# PIC.net
KiCad netlist of a schematic drawn in Altium Designer
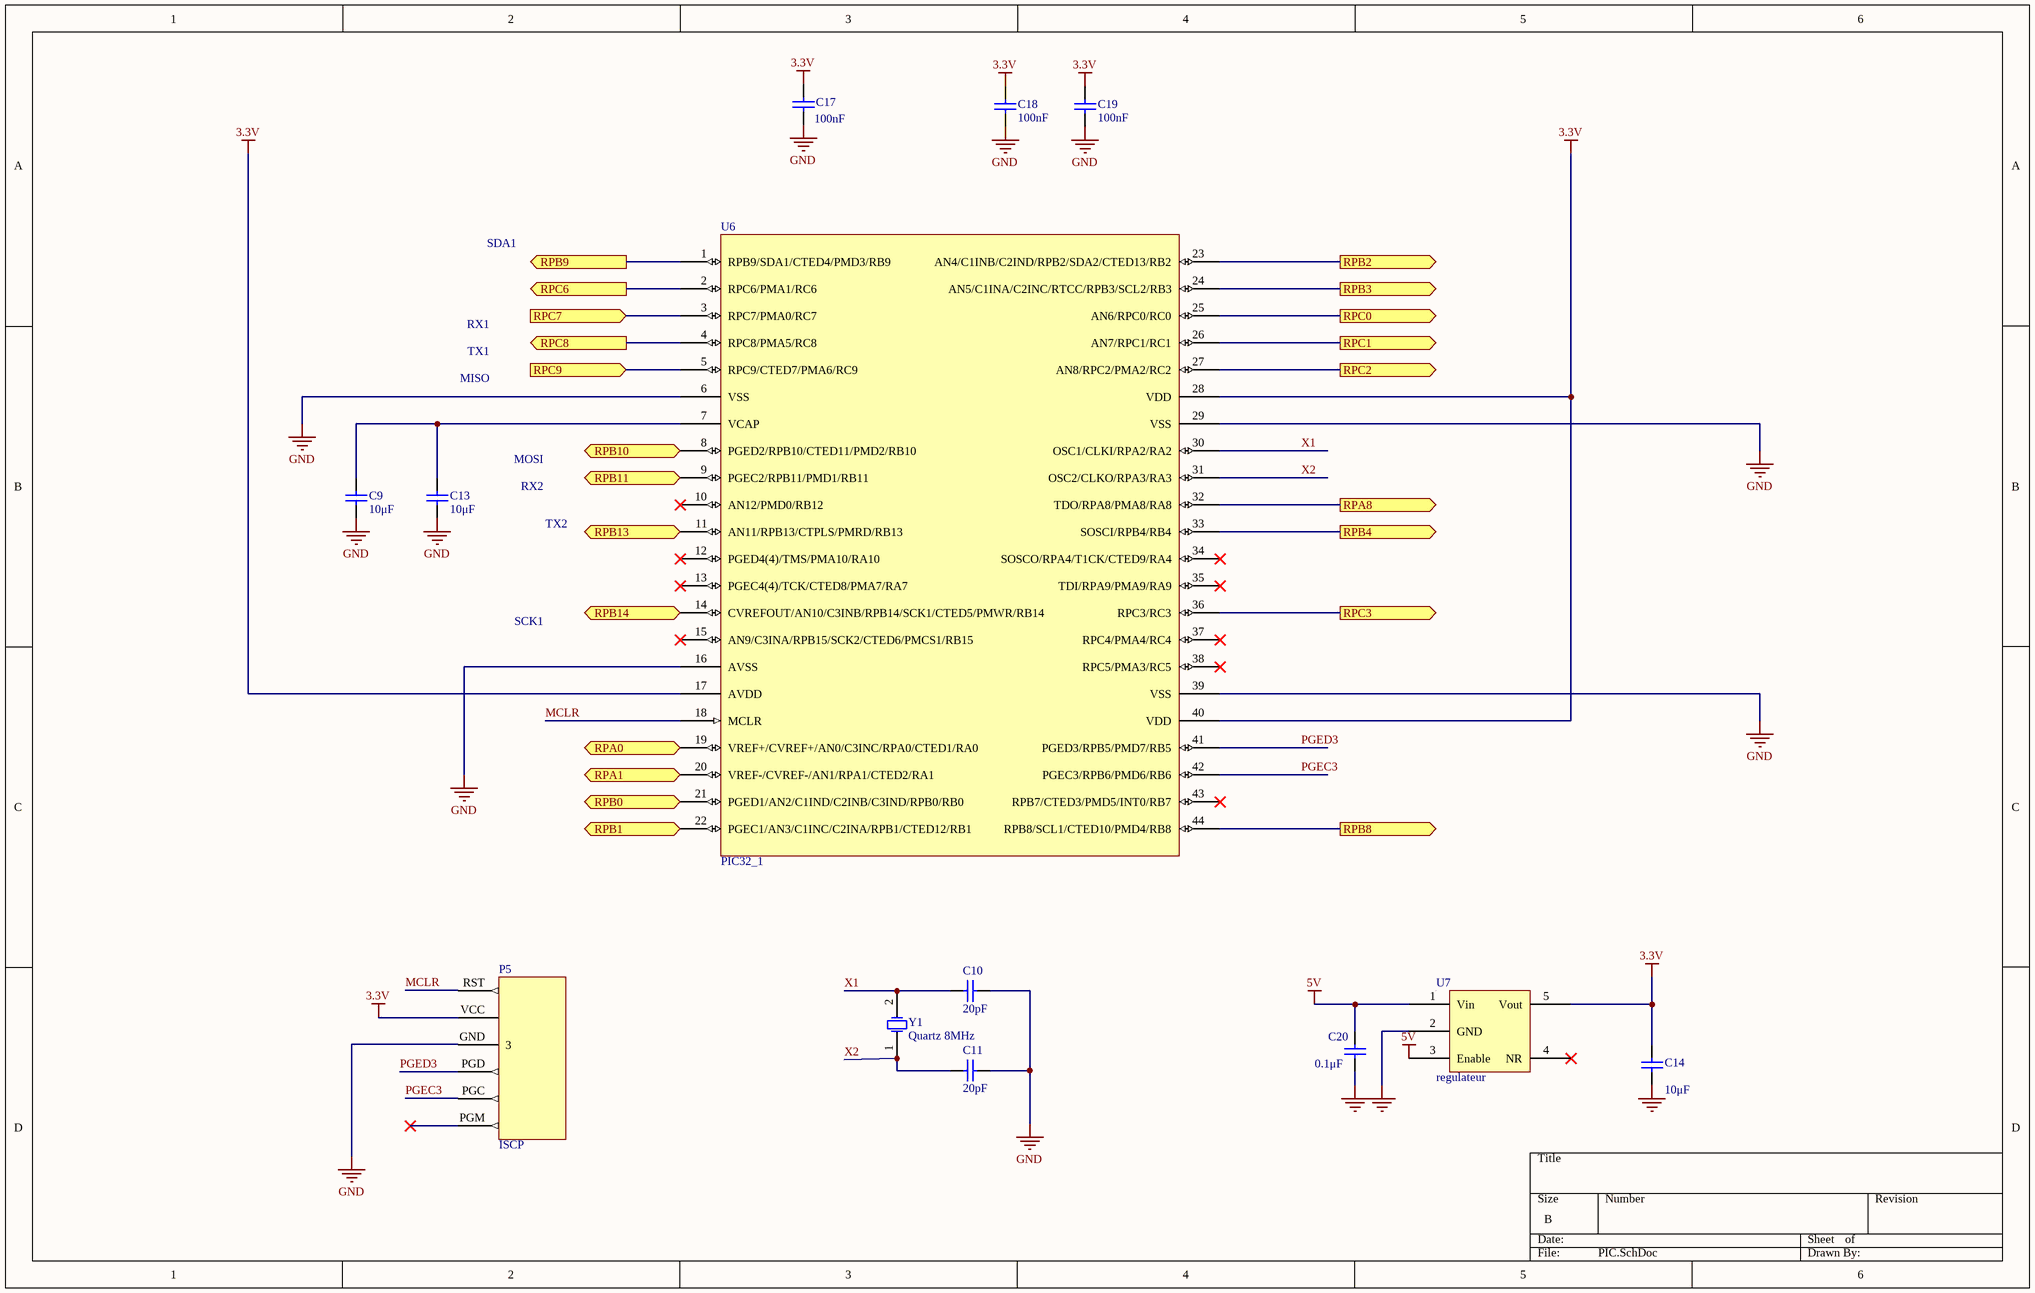
[diagram p0: PIC.SchDoc]

(export (version "E")
  (design (tool "Eeschema 10.0.6"))
  (components
    (comp (ref "C9")
      (value "10μF")
      (footprint "cond")
      (description "Capacitor")
      (fields (field (name "Comment") "Cap") (field (name "PUBLISHER") "Altium Limited"))
      (libsource (lib "Miscellaneous Devices") (part "Cap"))
    )
    (comp (ref "C10")
      (value "20pF")
      (footprint "cond")
      (description "Capacitor")
      (fields (field (name "Comment") "Cap") (field (name "PUBLISHER") "Altium Limited"))
      (libsource (lib "Miscellaneous Devices") (part "Cap"))
    )
    (comp (ref "C11")
      (value "20pF")
      (footprint "cond")
      (description "Capacitor")
      (fields (field (name "Comment") "Cap") (field (name "PUBLISHER") "Altium Limited"))
      (libsource (lib "Miscellaneous Devices") (part "Cap"))
    )
    (comp (ref "C13")
      (value "10μF")
      (footprint "cond")
      (description "Capacitor")
      (fields (field (name "Comment") "Cap") (field (name "PUBLISHER") "Altium Limited"))
      (libsource (lib "Miscellaneous Devices") (part "Cap"))
    )
    (comp (ref "C14")
      (value "10μF")
      (footprint "cond")
      (description "Capacitor")
      (fields (field (name "Comment") "Cap") (field (name "PUBLISHER") "Altium Limited"))
      (libsource (lib "Miscellaneous Devices") (part "Cap"))
    )
    (comp (ref "C17")
      (value "100nF")
      (footprint "cond")
      (description "Capacitor")
      (fields (field (name "Comment") "Cap") (field (name "PUBLISHER") "Altium Limited"))
      (libsource (lib "Miscellaneous Devices") (part "Cap"))
    )
    (comp (ref "C18")
      (value "100nF")
      (footprint "cond")
      (description "Capacitor")
      (fields (field (name "Comment") "Cap") (field (name "PUBLISHER") "Altium Limited"))
      (libsource (lib "Miscellaneous Devices") (part "Cap"))
    )
    (comp (ref "C19")
      (value "100nF")
      (footprint "cond")
      (description "Capacitor")
      (fields (field (name "Comment") "Cap") (field (name "PUBLISHER") "Altium Limited"))
      (libsource (lib "Miscellaneous Devices") (part "Cap"))
    )
    (comp (ref "C20")
      (value "0.1μF")
      (footprint "cond")
      (description "Capacitor")
      (fields (field (name "Comment") "Cap") (field (name "PUBLISHER") "Altium Limited"))
      (libsource (lib "Miscellaneous Devices") (part "Cap"))
    )
    (comp (ref "P5") (value "ISCP") (footprint "ISCP") (libsource (lib "Schlib1") (part "ISCP")))
    (comp (ref "U6") (value "PIC32_1") (libsource (lib "Schlib1") (part "PIC32_1")))
    (comp (ref "U7")
      (value "regulateur")
      (footprint "regulateur")
      (libsource (lib "Schlib1") (part "regulateur"))
    )
    (comp (ref "Y1")
      (value "Quartz 8MHz")
      (footprint "quartz")
      (description "Crystal Oscillator")
      (fields (field (name "PUBLISHER") "Altium Limited"))
      (libsource (lib "Miscellaneous Devices") (part "XTAL"))
    )
  )
  (nets
    (net (code "1") (name "/MCLR") (class "Default")
      (node (ref "P5") (pin "RST") (pinfunction "1_RST") (pintype "output"))
      (node (ref "U6") (pin "18") (pinfunction "MCLR_18") (pintype "input"))
    )
    (net (code "2") (name "/PGEC3") (class "Default")
      (node (ref "P5") (pin "PGC") (pinfunction "5_PGC") (pintype "output"))
      (node (ref "U6") (pin "42") (pinfunction "PGEC3/RPB6/PMD6/RB6_42") (pintype "bidirectional"))
    )
    (net (code "3") (name "/PGED3") (class "Default")
      (node (ref "P5") (pin "PGD") (pinfunction "4_PGD") (pintype "output"))
      (node (ref "U6") (pin "41") (pinfunction "PGED3/RPB5/PMD7/RB5_41") (pintype "bidirectional"))
    )
    (net (code "4") (name "/RPA0") (class "Default")
      (node (ref "U6") (pin "19") (pinfunction "VREF+/CVREF+/AN0/C3INC/RPA0/CTED1/RA0_19") (pintype "bidirectional"))
    )
    (net (code "5") (name "/RPA1") (class "Default")
      (node (ref "U6") (pin "20") (pinfunction "VREF-/CVREF-/AN1/RPA1/CTED2/RA1_20") (pintype "bidirectional"))
    )
    (net (code "6") (name "/RPA8") (class "Default")
      (node (ref "U6") (pin "32") (pinfunction "TDO/RPA8/PMA8/RA8_32") (pintype "bidirectional"))
    )
    (net (code "7") (name "/RPB0") (class "Default")
      (node (ref "U6") (pin "21") (pinfunction "PGED1/AN2/C1IND/C2INB/C3IND/RPB0/RB0_21") (pintype "bidirectional"))
    )
    (net (code "8") (name "/RPB1") (class "Default")
      (node (ref "U6") (pin "22") (pinfunction "PGEC1/AN3/C1INC/C2INA/RPB1/CTED12/RB1_22") (pintype "bidirectional"))
    )
    (net (code "9") (name "/RPB2") (class "Default")
      (node (ref "U6") (pin "23") (pinfunction "AN4/C1INB/C2IND/RPB2/SDA2/CTED13/RB2_23") (pintype "bidirectional"))
    )
    (net (code "10") (name "/RPB3") (class "Default")
      (node (ref "U6") (pin "24") (pinfunction "AN5/C1INA/C2INC/RTCC/RPB3/SCL2/RB3_24") (pintype "bidirectional"))
    )
    (net (code "11") (name "/RPB4") (class "Default")
      (node (ref "U6") (pin "33") (pinfunction "SOSCI/RPB4/RB4_33") (pintype "bidirectional"))
    )
    (net (code "12") (name "/RPB8") (class "Default")
      (node (ref "U6") (pin "44") (pinfunction "RPB8/SCL1/CTED10/PMD4/RB8_44") (pintype "bidirectional"))
    )
    (net (code "13") (name "/RPB9") (class "Default")
      (node (ref "U6") (pin "1") (pinfunction "RPB9/SDA1/CTED4/PMD3/RB9_1") (pintype "bidirectional"))
    )
    (net (code "14") (name "/RPB10") (class "Default")
      (node (ref "U6") (pin "8") (pinfunction "PGED2/RPB10/CTED11/PMD2/RB10_8") (pintype "bidirectional"))
    )
    (net (code "15") (name "/RPB11") (class "Default")
      (node (ref "U6") (pin "9") (pinfunction "PGEC2/RPB11/PMD1/RB11_9") (pintype "bidirectional"))
    )
    (net (code "16") (name "/RPB13") (class "Default")
      (node (ref "U6") (pin "11") (pinfunction "AN11/RPB13/CTPLS/PMRD/RB13_11") (pintype "bidirectional"))
    )
    (net (code "17") (name "/RPB14") (class "Default")
      (node (ref "U6") (pin "14") (pinfunction "CVREFOUT/AN10/C3INB/RPB14/SCK1/CTED5/PMWR/RB14_14") (pintype "bidirectional"))
    )
    (net (code "18") (name "/RPC0") (class "Default")
      (node (ref "U6") (pin "25") (pinfunction "AN6/RPC0/RC0_25") (pintype "bidirectional"))
    )
    (net (code "19") (name "/RPC1") (class "Default")
      (node (ref "U6") (pin "26") (pinfunction "AN7/RPC1/RC1_26") (pintype "bidirectional"))
    )
    (net (code "20") (name "/RPC2") (class "Default")
      (node (ref "U6") (pin "27") (pinfunction "AN8/RPC2/PMA2/RC2_27") (pintype "bidirectional"))
    )
    (net (code "21") (name "/RPC3") (class "Default")
      (node (ref "U6") (pin "36") (pinfunction "RPC3/RC3_36") (pintype "bidirectional"))
    )
    (net (code "22") (name "/RPC6") (class "Default")
      (node (ref "U6") (pin "2") (pinfunction "RPC6/PMA1/RC6_2") (pintype "bidirectional"))
    )
    (net (code "23") (name "/RPC7") (class "Default")
      (node (ref "U6") (pin "3") (pinfunction "RPC7/PMA0/RC7_3") (pintype "bidirectional"))
    )
    (net (code "24") (name "/RPC8") (class "Default")
      (node (ref "U6") (pin "4") (pinfunction "RPC8/PMA5/RC8_4") (pintype "bidirectional"))
    )
    (net (code "25") (name "/RPC9") (class "Default")
      (node (ref "U6") (pin "5") (pinfunction "RPC9/CTED7/PMA6/RC9_5") (pintype "bidirectional"))
    )
    (net (code "26") (name "/X1") (class "Default")
      (node (ref "C10") (pin "2") (pinfunction "2_2") (pintype "passive"))
      (node (ref "U6") (pin "30") (pinfunction "OSC1/CLKI/RPA2/RA2_30") (pintype "bidirectional"))
      (node (ref "Y1") (pin "2") (pinfunction "OSC2_2") (pintype "passive"))
    )
    (net (code "27") (name "/X2") (class "Default")
      (node (ref "C11") (pin "2") (pinfunction "2_2") (pintype "passive"))
      (node (ref "U6") (pin "31") (pinfunction "OSC2/CLKO/RPA3/RA3_31") (pintype "bidirectional"))
      (node (ref "Y1") (pin "1") (pinfunction "OSC1_1") (pintype "passive"))
    )
    (net (code "28") (name "3.3V") (class "Default")
      (node (ref "C14") (pin "2") (pinfunction "2_2") (pintype "passive"))
      (node (ref "C17") (pin "2") (pinfunction "2_2") (pintype "passive"))
      (node (ref "C18") (pin "1") (pinfunction "1_1") (pintype "passive"))
      (node (ref "C19") (pin "1") (pinfunction "1_1") (pintype "passive"))
      (node (ref "P5") (pin "VCC") (pinfunction "2_VCC") (pintype "passive"))
      (node (ref "U6") (pin "17") (pinfunction "AVDD_17") (pintype "passive"))
      (node (ref "U6") (pin "28") (pinfunction "VDD_28") (pintype "passive"))
      (node (ref "U6") (pin "40") (pinfunction "VDD_40") (pintype "passive"))
      (node (ref "U7") (pin "5") (pinfunction "Vout_5") (pintype "passive"))
    )
    (net (code "29") (name "5V") (class "Default")
      (node (ref "C20") (pin "2") (pinfunction "2_2") (pintype "passive"))
      (node (ref "U7") (pin "1") (pinfunction "Vin_1") (pintype "power_in"))
      (node (ref "U7") (pin "3") (pinfunction "Enable_3") (pintype "passive"))
    )
    (net (code "30") (name "GND") (class "Default")
      (node (ref "C10") (pin "1") (pinfunction "1_1") (pintype "passive"))
      (node (ref "C11") (pin "1") (pinfunction "1_1") (pintype "passive"))
      (node (ref "C13") (pin "2") (pinfunction "2_2") (pintype "passive"))
      (node (ref "C14") (pin "1") (pinfunction "1_1") (pintype "passive"))
      (node (ref "C17") (pin "1") (pinfunction "1_1") (pintype "passive"))
      (node (ref "C18") (pin "2") (pinfunction "2_2") (pintype "passive"))
      (node (ref "C19") (pin "2") (pinfunction "2_2") (pintype "passive"))
      (node (ref "C20") (pin "1") (pinfunction "1_1") (pintype "passive"))
      (node (ref "C9") (pin "2") (pinfunction "2_2") (pintype "passive"))
      (node (ref "P5") (pin "GND") (pinfunction "3_GND") (pintype "passive"))
      (node (ref "U6") (pin "16") (pinfunction "AVSS_16") (pintype "passive"))
      (node (ref "U6") (pin "29") (pinfunction "VSS_29") (pintype "power_in"))
      (node (ref "U6") (pin "39") (pinfunction "VSS_39") (pintype "power_in"))
      (node (ref "U6") (pin "6") (pinfunction "VSS_6") (pintype "passive"))
      (node (ref "U7") (pin "2") (pinfunction "GND_2") (pintype "passive"))
    )
    (net (code "31") (name "Net-(U6-VCAP)") (class "Default")
      (node (ref "C13") (pin "1") (pinfunction "1_1") (pintype "passive"))
      (node (ref "C9") (pin "1") (pinfunction "1_1") (pintype "passive"))
      (node (ref "U6") (pin "7") (pinfunction "VCAP_7") (pintype "passive"))
    )
    (net (code "32") (name "unconnected-(P5-6-PadPGM)") (class "Default")
      (node (ref "P5") (pin "PGM") (pinfunction "6_PGM") (pintype "output+no_connect"))
    )
    (net (code "33") (name "unconnected-(U6-AN9{slash}C3INA{slash}RPB15{slash}SCK2{slash}CTED6{slash}PMCS1{slash}RB15-Pad15)") (class "Default")
      (node (ref "U6") (pin "15") (pinfunction "AN9/C3INA/RPB15/SCK2/CTED6/PMCS1/RB15_15") (pintype "bidirectional+no_connect"))
    )
    (net (code "34") (name "unconnected-(U6-AN12{slash}PMD0{slash}RB12-Pad10)") (class "Default")
      (node (ref "U6") (pin "10") (pinfunction "AN12/PMD0/RB12_10") (pintype "bidirectional+no_connect"))
    )
    (net (code "35") (name "unconnected-(U6-PGEC4(4){slash}TCK{slash}CTED8{slash}PMA7{slash}RA7-Pad13)") (class "Default")
      (node (ref "U6") (pin "13") (pinfunction "PGEC4(4)/TCK/CTED8/PMA7/RA7_13") (pintype "bidirectional+no_connect"))
    )
    (net (code "36") (name "unconnected-(U6-PGED4(4){slash}TMS{slash}PMA10{slash}RA10-Pad12)") (class "Default")
      (node (ref "U6") (pin "12") (pinfunction "PGED4(4)/TMS/PMA10/RA10_12") (pintype "bidirectional+no_connect"))
    )
    (net (code "37") (name "unconnected-(U6-RPB7{slash}CTED3{slash}PMD5{slash}INT0{slash}RB7-Pad43)") (class "Default")
      (node (ref "U6") (pin "43") (pinfunction "RPB7/CTED3/PMD5/INT0/RB7_43") (pintype "bidirectional+no_connect"))
    )
    (net (code "38") (name "unconnected-(U6-RPC4{slash}PMA4{slash}RC4-Pad37)") (class "Default")
      (node (ref "U6") (pin "37") (pinfunction "RPC4/PMA4/RC4_37") (pintype "bidirectional+no_connect"))
    )
    (net (code "39") (name "unconnected-(U6-RPC5{slash}PMA3{slash}RC5-Pad38)") (class "Default")
      (node (ref "U6") (pin "38") (pinfunction "RPC5/PMA3/RC5_38") (pintype "bidirectional+no_connect"))
    )
    (net (code "40") (name "unconnected-(U6-SOSCO{slash}RPA4{slash}T1CK{slash}CTED9{slash}RA4-Pad34)") (class "Default")
      (node (ref "U6") (pin "34") (pinfunction "SOSCO/RPA4/T1CK/CTED9/RA4_34") (pintype "bidirectional+no_connect"))
    )
    (net (code "41") (name "unconnected-(U6-TDI{slash}RPA9{slash}PMA9{slash}RA9-Pad35)") (class "Default")
      (node (ref "U6") (pin "35") (pinfunction "TDI/RPA9/PMA9/RA9_35") (pintype "bidirectional+no_connect"))
    )
    (net (code "42") (name "unconnected-(U7-NR-Pad4)") (class "Default")
      (node (ref "U7") (pin "4") (pinfunction "NR_4") (pintype "passive+no_connect"))
    )
  )
)
